# Page07_CPU_PHY.net
KiCad netlist of a schematic drawn in Altium Designer
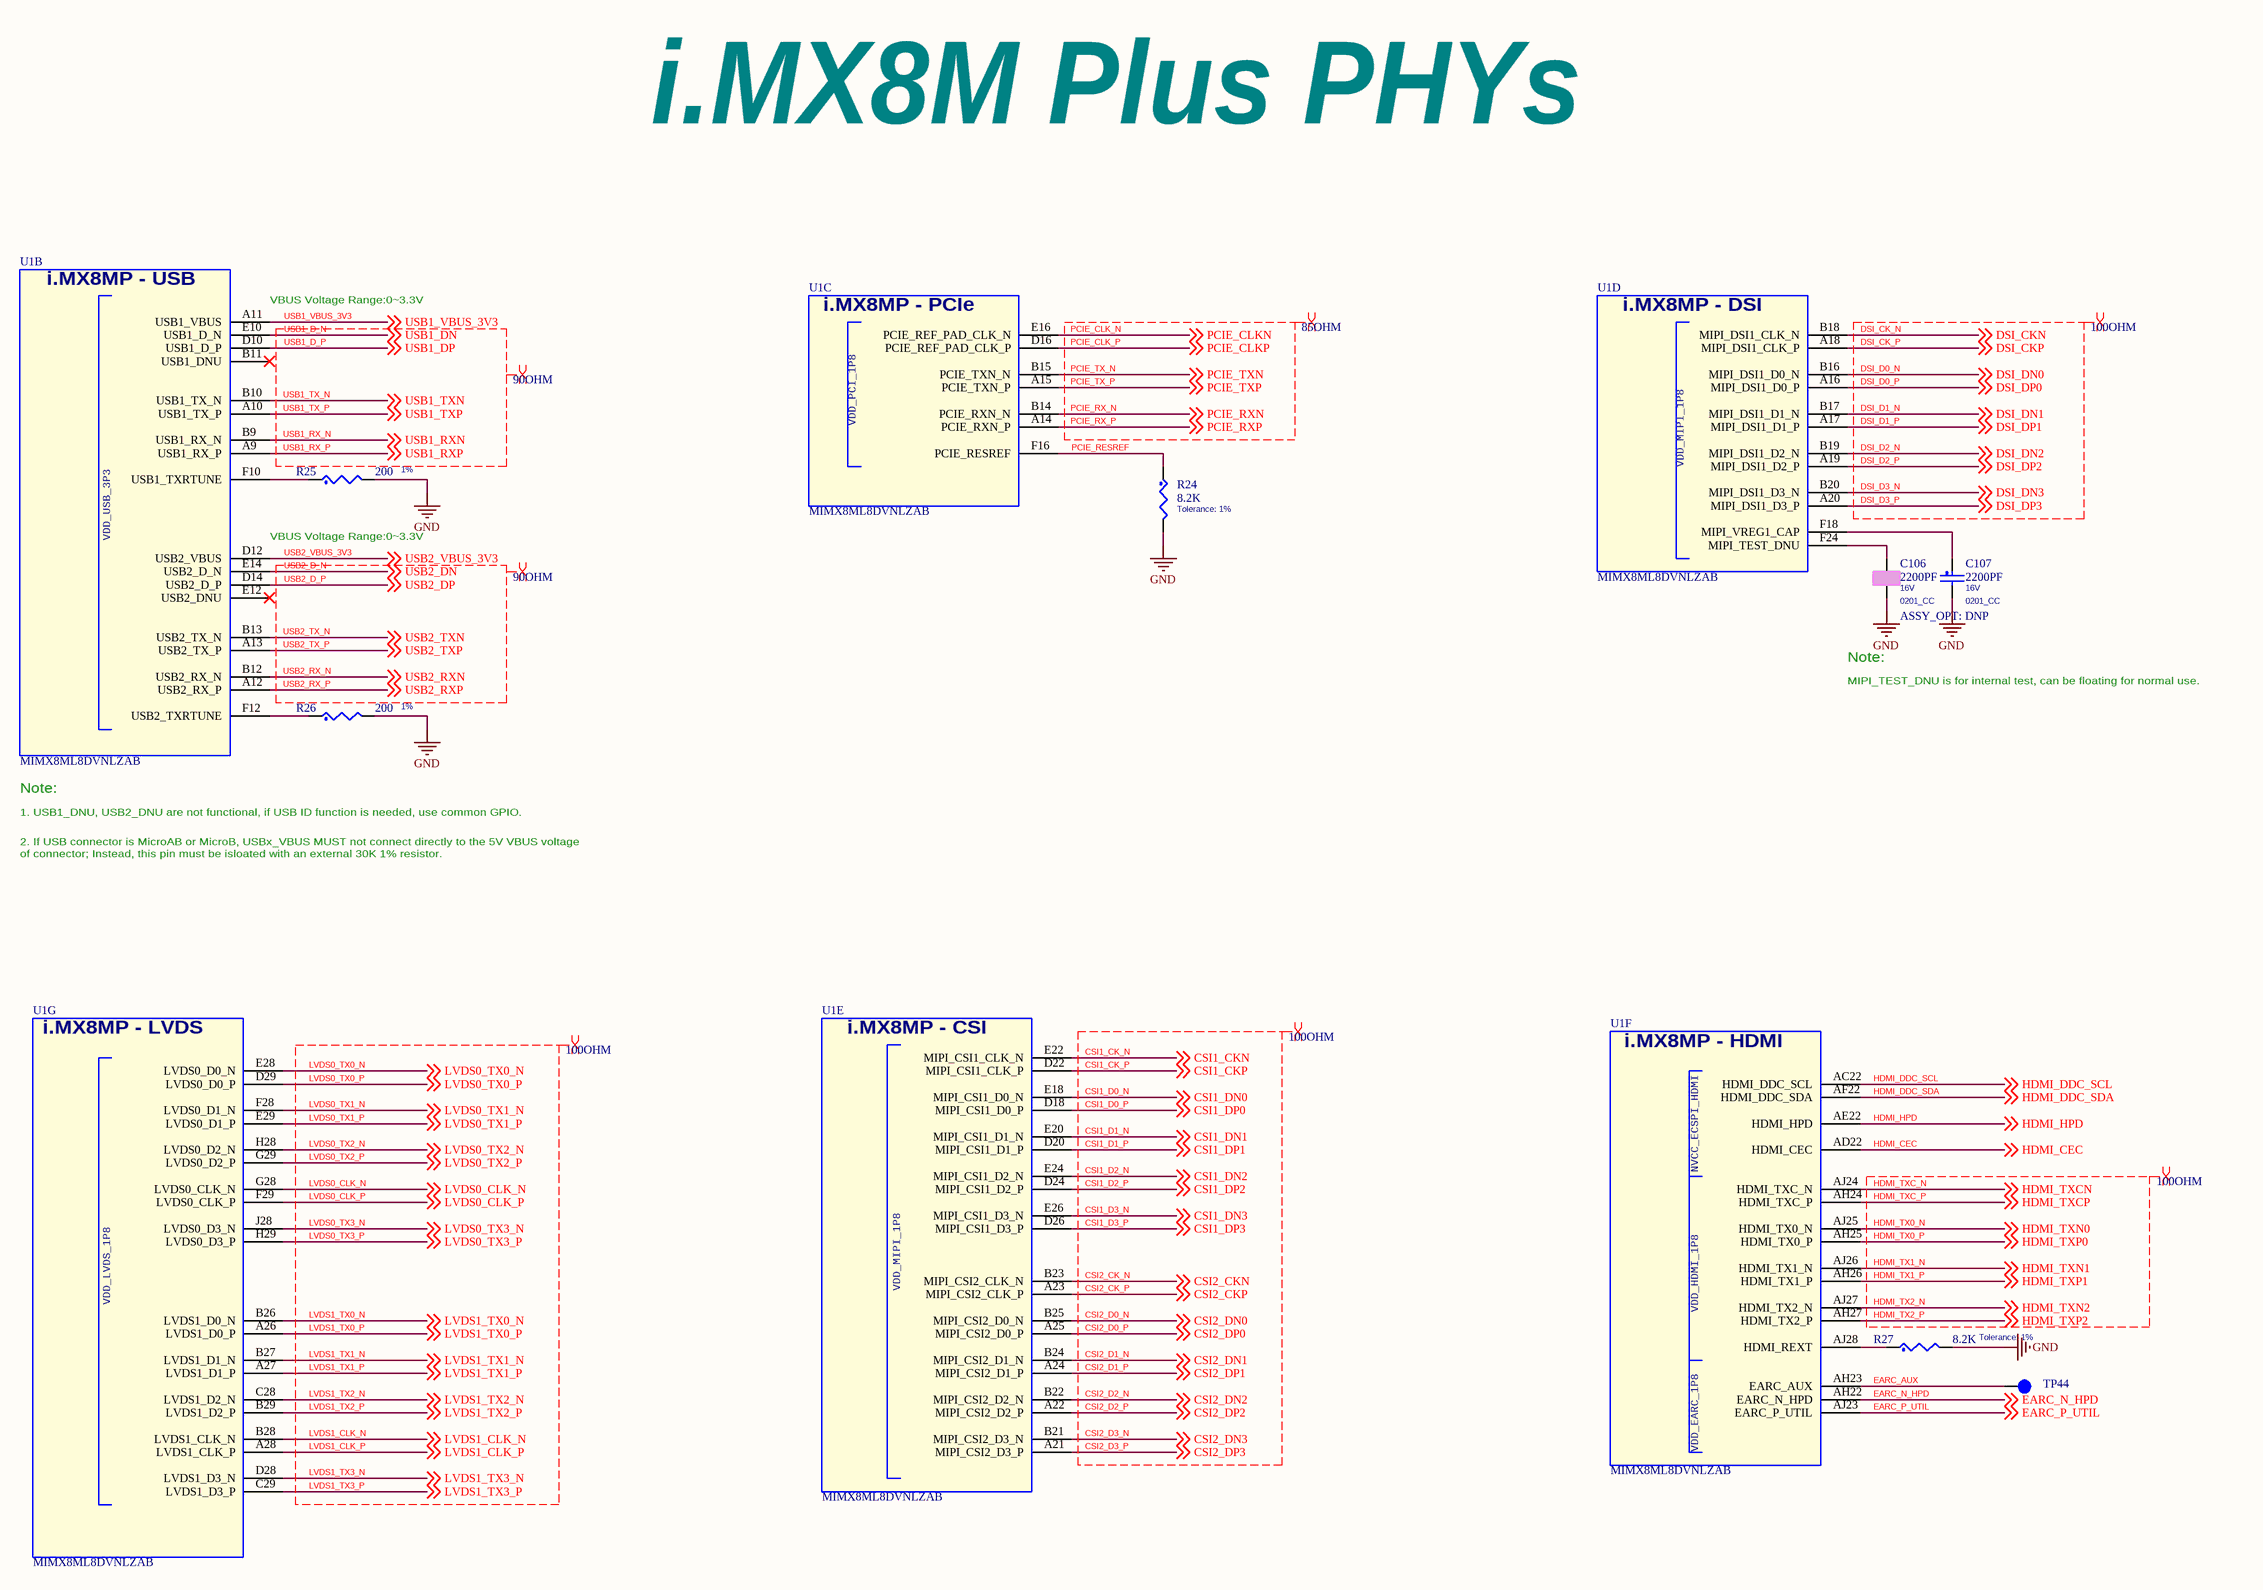
[diagram p0: Page07 CPU PHY.SchDoc]

(export (version "E")
  (design (tool "Eeschema 10.0.6"))
  (components
    (comp (ref "C106")
      (value "2200PF")
      (footprint "0201_CC")
      (description "CAP CER 2200PF 16V 10% X7R 0201")
      (fields
        (field (name "ASSY_OPT") "DNP")
        (field (name "PCB FOOTPRINT") "0201_CC")
        (field (name "VOLTAGE") "16V")
        (field (name "TOLERANCE") "20%")
      )
      (libsource (lib "*") (part "CAP_NP"))
    )
    (comp (ref "C107")
      (value "2200PF")
      (footprint "0201_CC")
      (description "CAP CER 2200PF 16V 10% X7R 0201")
      (fields
        (field (name "PCB FOOTPRINT") "0201_CC")
        (field (name "TOLERANCE") "20%")
        (field (name "VOLTAGE") "16V")
      )
      (libsource (lib "*") (part "CAP_NP"))
    )
    (comp (ref "R24")
      (value "8.2K")
      (footprint "0201_CC")
      (description "RES MF 8.2K 1/20W 1% 0201")
      (fields (field (name "TOLERANCE") "1%"))
      (libsource (lib "*") (part "RES"))
    )
    (comp (ref "R25")
      (value "200")
      (footprint "0201_CC")
      (description "RES MF 200 OHM 1/20W 1% 0201")
      (fields (field (name "TOLERANCE") "1%") (field (name "VOLTAGE") "25V"))
      (libsource (lib "*") (part "RES"))
    )
    (comp (ref "R26")
      (value "200")
      (footprint "0201_CC")
      (description "RES MF 200 OHM 1/20W 1% 0201")
      (fields (field (name "TOLERANCE") "1%") (field (name "VOLTAGE") "25V"))
      (libsource (lib "*") (part "RES"))
    )
    (comp (ref "R27")
      (value "8.2K")
      (footprint "0201_CC")
      (description "RES MF 8.2K 1/20W 1% 0201")
      (fields (field (name "TOLERANCE") "1%"))
      (libsource (lib "*") (part "RES"))
    )
    (comp (ref "TP44")
      (value "tpad_020")
      (footprint "tpad_020")
      (description "TEST POINT PAD 0.5MM DIA SMT, NO PART TO ORDER")
      (libsource (lib "*") (part "TESTLOOP"))
    )
    (comp (ref "U1")
      (value "MIMX8ML8DVNLZAB")
      (footprint "BGA_M865S_0P5_15X15-BMS")
      (description "IC CPU QUAD CORTEX A53+M4 1.8GHZ BGA548")
      (libsource (lib "*") (part "MIMX8MP_BGA548"))
    )
  )
  (nets
    (net (code "1") (name "/EARC_AUX") (class "Default")
      (node (ref "TP44") (pin "1") (pinfunction "Pin1_1") (pintype "passive"))
      (node (ref "U1") (pin "AH23") (pinfunction "EARC_AUX_AH23") (pintype "passive"))
    )
    (net (code "2") (name "/PCIE_RESREF") (class "Default")
      (node (ref "R24") (pin "1") (pinfunction "1_1") (pintype "passive"))
      (node (ref "U1") (pin "F16") (pinfunction "PCIE_RESREF_F16") (pintype "passive"))
    )
    (net (code "3") (name "CSI1_CKN") (class "Default")
      (node (ref "U1") (pin "E22") (pinfunction "MIPI_CSI1_CLK_N_E22") (pintype "passive"))
    )
    (net (code "4") (name "CSI1_CKP") (class "Default")
      (node (ref "U1") (pin "D22") (pinfunction "MIPI_CSI1_CLK_P_D22") (pintype "passive"))
    )
    (net (code "5") (name "CSI1_DN0") (class "Default")
      (node (ref "U1") (pin "E18") (pinfunction "MIPI_CSI1_D0_N_E18") (pintype "passive"))
    )
    (net (code "6") (name "CSI1_DN1") (class "Default")
      (node (ref "U1") (pin "E20") (pinfunction "MIPI_CSI1_D1_N_E20") (pintype "passive"))
    )
    (net (code "7") (name "CSI1_DN2") (class "Default")
      (node (ref "U1") (pin "E24") (pinfunction "MIPI_CSI1_D2_N_E24") (pintype "passive"))
    )
    (net (code "8") (name "CSI1_DN3") (class "Default")
      (node (ref "U1") (pin "E26") (pinfunction "MIPI_CSI1_D3_N_E26") (pintype "passive"))
    )
    (net (code "9") (name "CSI1_DP0") (class "Default")
      (node (ref "U1") (pin "D18") (pinfunction "MIPI_CSI1_D0_P_D18") (pintype "passive"))
    )
    (net (code "10") (name "CSI1_DP1") (class "Default")
      (node (ref "U1") (pin "D20") (pinfunction "MIPI_CSI1_D1_P_D20") (pintype "passive"))
    )
    (net (code "11") (name "CSI1_DP2") (class "Default")
      (node (ref "U1") (pin "D24") (pinfunction "MIPI_CSI1_D2_P_D24") (pintype "passive"))
    )
    (net (code "12") (name "CSI1_DP3") (class "Default")
      (node (ref "U1") (pin "D26") (pinfunction "MIPI_CSI1_D3_P_D26") (pintype "passive"))
    )
    (net (code "13") (name "CSI2_CKN") (class "Default")
      (node (ref "U1") (pin "B23") (pinfunction "MIPI_CSI2_CLK_N_B23") (pintype "passive"))
    )
    (net (code "14") (name "CSI2_CKP") (class "Default")
      (node (ref "U1") (pin "A23") (pinfunction "MIPI_CSI2_CLK_P_A23") (pintype "passive"))
    )
    (net (code "15") (name "CSI2_DN0") (class "Default")
      (node (ref "U1") (pin "B25") (pinfunction "MIPI_CSI2_D0_N_B25") (pintype "passive"))
    )
    (net (code "16") (name "CSI2_DN1") (class "Default")
      (node (ref "U1") (pin "B24") (pinfunction "MIPI_CSI2_D1_N_B24") (pintype "passive"))
    )
    (net (code "17") (name "CSI2_DN2") (class "Default")
      (node (ref "U1") (pin "B22") (pinfunction "MIPI_CSI2_D2_N_B22") (pintype "passive"))
    )
    (net (code "18") (name "CSI2_DN3") (class "Default")
      (node (ref "U1") (pin "B21") (pinfunction "MIPI_CSI2_D3_N_B21") (pintype "passive"))
    )
    (net (code "19") (name "CSI2_DP0") (class "Default")
      (node (ref "U1") (pin "A25") (pinfunction "MIPI_CSI2_D0_P_A25") (pintype "passive"))
    )
    (net (code "20") (name "CSI2_DP1") (class "Default")
      (node (ref "U1") (pin "A24") (pinfunction "MIPI_CSI2_D1_P_A24") (pintype "passive"))
    )
    (net (code "21") (name "CSI2_DP2") (class "Default")
      (node (ref "U1") (pin "A22") (pinfunction "MIPI_CSI2_D2_P_A22") (pintype "passive"))
    )
    (net (code "22") (name "CSI2_DP3") (class "Default")
      (node (ref "U1") (pin "A21") (pinfunction "MIPI_CSI2_D3_P_A21") (pintype "passive"))
    )
    (net (code "23") (name "DSI_CKN") (class "Default")
      (node (ref "U1") (pin "B18") (pinfunction "MIPI_DSI1_CLK_N_B18") (pintype "passive"))
    )
    (net (code "24") (name "DSI_CKP") (class "Default")
      (node (ref "U1") (pin "A18") (pinfunction "MIPI_DSI1_CLK_P_A18") (pintype "passive"))
    )
    (net (code "25") (name "DSI_DN0") (class "Default")
      (node (ref "U1") (pin "B16") (pinfunction "MIPI_DSI1_D0_N_B16") (pintype "passive"))
    )
    (net (code "26") (name "DSI_DN1") (class "Default")
      (node (ref "U1") (pin "B17") (pinfunction "MIPI_DSI1_D1_N_B17") (pintype "passive"))
    )
    (net (code "27") (name "DSI_DN2") (class "Default")
      (node (ref "U1") (pin "B19") (pinfunction "MIPI_DSI1_D2_N_B19") (pintype "passive"))
    )
    (net (code "28") (name "DSI_DN3") (class "Default")
      (node (ref "U1") (pin "B20") (pinfunction "MIPI_DSI1_D3_N_B20") (pintype "passive"))
    )
    (net (code "29") (name "DSI_DP0") (class "Default")
      (node (ref "U1") (pin "A16") (pinfunction "MIPI_DSI1_D0_P_A16") (pintype "passive"))
    )
    (net (code "30") (name "DSI_DP1") (class "Default")
      (node (ref "U1") (pin "A17") (pinfunction "MIPI_DSI1_D1_P_A17") (pintype "passive"))
    )
    (net (code "31") (name "DSI_DP2") (class "Default")
      (node (ref "U1") (pin "A19") (pinfunction "MIPI_DSI1_D2_P_A19") (pintype "passive"))
    )
    (net (code "32") (name "DSI_DP3") (class "Default")
      (node (ref "U1") (pin "A20") (pinfunction "MIPI_DSI1_D3_P_A20") (pintype "passive"))
    )
    (net (code "33") (name "EARC_N_HPD") (class "Default")
      (node (ref "U1") (pin "AH22") (pinfunction "EARC_N_HPD_AH22") (pintype "passive"))
    )
    (net (code "34") (name "EARC_P_UTIL") (class "Default")
      (node (ref "U1") (pin "AJ23") (pinfunction "EARC_P_UTIL_AJ23") (pintype "passive"))
    )
    (net (code "35") (name "GND") (class "Default")
      (node (ref "C106") (pin "2") (pinfunction "2_2") (pintype "passive"))
      (node (ref "C107") (pin "2") (pinfunction "2_2") (pintype "passive"))
      (node (ref "R24") (pin "2") (pinfunction "2_2") (pintype "passive"))
      (node (ref "R25") (pin "2") (pinfunction "2_2") (pintype "passive"))
      (node (ref "R26") (pin "2") (pinfunction "2_2") (pintype "passive"))
      (node (ref "R27") (pin "2") (pinfunction "2_2") (pintype "passive"))
    )
    (net (code "36") (name "HDMI_CEC") (class "Default")
      (node (ref "U1") (pin "AD22") (pinfunction "HDMI_CEC_AD22") (pintype "passive"))
    )
    (net (code "37") (name "HDMI_DDC_SCL") (class "Default")
      (node (ref "U1") (pin "AC22") (pinfunction "HDMI_DDC_SCL_AC22") (pintype "passive"))
    )
    (net (code "38") (name "HDMI_DDC_SDA") (class "Default")
      (node (ref "U1") (pin "AF22") (pinfunction "HDMI_DDC_SDA_AF22") (pintype "passive"))
    )
    (net (code "39") (name "HDMI_HPD") (class "Default")
      (node (ref "U1") (pin "AE22") (pinfunction "HDMI_HPD_AE22") (pintype "passive"))
    )
    (net (code "40") (name "HDMI_TXCN") (class "Default")
      (node (ref "U1") (pin "AJ24") (pinfunction "HDMI_TXC_N_AJ24") (pintype "passive"))
    )
    (net (code "41") (name "HDMI_TXCP") (class "Default")
      (node (ref "U1") (pin "AH24") (pinfunction "HDMI_TXC_P_AH24") (pintype "passive"))
    )
    (net (code "42") (name "HDMI_TXN0") (class "Default")
      (node (ref "U1") (pin "AJ25") (pinfunction "HDMI_TX0_N_AJ25") (pintype "passive"))
    )
    (net (code "43") (name "HDMI_TXN1") (class "Default")
      (node (ref "U1") (pin "AJ26") (pinfunction "HDMI_TX1_N_AJ26") (pintype "passive"))
    )
    (net (code "44") (name "HDMI_TXN2") (class "Default")
      (node (ref "U1") (pin "AJ27") (pinfunction "HDMI_TX2_N_AJ27") (pintype "passive"))
    )
    (net (code "45") (name "HDMI_TXP0") (class "Default")
      (node (ref "U1") (pin "AH25") (pinfunction "HDMI_TX0_P_AH25") (pintype "passive"))
    )
    (net (code "46") (name "HDMI_TXP1") (class "Default")
      (node (ref "U1") (pin "AH26") (pinfunction "HDMI_TX1_P_AH26") (pintype "passive"))
    )
    (net (code "47") (name "HDMI_TXP2") (class "Default")
      (node (ref "U1") (pin "AH27") (pinfunction "HDMI_TX2_P_AH27") (pintype "passive"))
    )
    (net (code "48") (name "LVDS0_CLK_N") (class "Default")
      (node (ref "U1") (pin "G28") (pinfunction "LVDS0_CLK_N_G28") (pintype "passive"))
    )
    (net (code "49") (name "LVDS0_CLK_P") (class "Default")
      (node (ref "U1") (pin "F29") (pinfunction "LVDS0_CLK_P_F29") (pintype "passive"))
    )
    (net (code "50") (name "LVDS0_TX0_N") (class "Default")
      (node (ref "U1") (pin "E28") (pinfunction "LVDS0_D0_N_E28") (pintype "passive"))
    )
    (net (code "51") (name "LVDS0_TX0_P") (class "Default")
      (node (ref "U1") (pin "D29") (pinfunction "LVDS0_D0_P_D29") (pintype "passive"))
    )
    (net (code "52") (name "LVDS0_TX1_N") (class "Default")
      (node (ref "U1") (pin "F28") (pinfunction "LVDS0_D1_N_F28") (pintype "passive"))
    )
    (net (code "53") (name "LVDS0_TX1_P") (class "Default")
      (node (ref "U1") (pin "E29") (pinfunction "LVDS0_D1_P_E29") (pintype "passive"))
    )
    (net (code "54") (name "LVDS0_TX2_N") (class "Default")
      (node (ref "U1") (pin "H28") (pinfunction "LVDS0_D2_N_H28") (pintype "passive"))
    )
    (net (code "55") (name "LVDS0_TX2_P") (class "Default")
      (node (ref "U1") (pin "G29") (pinfunction "LVDS0_D2_P_G29") (pintype "passive"))
    )
    (net (code "56") (name "LVDS0_TX3_N") (class "Default")
      (node (ref "U1") (pin "J28") (pinfunction "LVDS0_D3_N_J28") (pintype "passive"))
    )
    (net (code "57") (name "LVDS0_TX3_P") (class "Default")
      (node (ref "U1") (pin "H29") (pinfunction "LVDS0_D3_P_H29") (pintype "passive"))
    )
    (net (code "58") (name "LVDS1_CLK_N") (class "Default")
      (node (ref "U1") (pin "B28") (pinfunction "LVDS1_CLK_N_B28") (pintype "passive"))
    )
    (net (code "59") (name "LVDS1_CLK_P") (class "Default")
      (node (ref "U1") (pin "A28") (pinfunction "LVDS1_CLK_P_A28") (pintype "passive"))
    )
    (net (code "60") (name "LVDS1_TX0_N") (class "Default")
      (node (ref "U1") (pin "B26") (pinfunction "LVDS1_D0_N_B26") (pintype "passive"))
    )
    (net (code "61") (name "LVDS1_TX0_P") (class "Default")
      (node (ref "U1") (pin "A26") (pinfunction "LVDS1_D0_P_A26") (pintype "passive"))
    )
    (net (code "62") (name "LVDS1_TX1_N") (class "Default")
      (node (ref "U1") (pin "B27") (pinfunction "LVDS1_D1_N_B27") (pintype "passive"))
    )
    (net (code "63") (name "LVDS1_TX1_P") (class "Default")
      (node (ref "U1") (pin "A27") (pinfunction "LVDS1_D1_P_A27") (pintype "passive"))
    )
    (net (code "64") (name "LVDS1_TX2_N") (class "Default")
      (node (ref "U1") (pin "C28") (pinfunction "LVDS1_D2_N_C28") (pintype "passive"))
    )
    (net (code "65") (name "LVDS1_TX2_P") (class "Default")
      (node (ref "U1") (pin "B29") (pinfunction "LVDS1_D2_P_B29") (pintype "passive"))
    )
    (net (code "66") (name "LVDS1_TX3_N") (class "Default")
      (node (ref "U1") (pin "D28") (pinfunction "LVDS1_D3_N_D28") (pintype "passive"))
    )
    (net (code "67") (name "LVDS1_TX3_P") (class "Default")
      (node (ref "U1") (pin "C29") (pinfunction "LVDS1_D3_P_C29") (pintype "passive"))
    )
    (net (code "68") (name "Net-(U1B-USB1_TXRTUNE)") (class "Default")
      (node (ref "R25") (pin "1") (pinfunction "1_1") (pintype "passive"))
      (node (ref "U1") (pin "F10") (pinfunction "USB1_TXRTUNE_F10") (pintype "passive"))
    )
    (net (code "69") (name "Net-(U1B-USB2_TXRTUNE)") (class "Default")
      (node (ref "R26") (pin "1") (pinfunction "1_1") (pintype "passive"))
      (node (ref "U1") (pin "F12") (pinfunction "USB2_TXRTUNE_F12") (pintype "passive"))
    )
    (net (code "70") (name "Net-(U1D-MIPI_TEST_DNU)") (class "Default")
      (node (ref "C106") (pin "1") (pinfunction "1_1") (pintype "passive"))
      (node (ref "U1") (pin "F24") (pinfunction "MIPI_TEST_DNU_F24") (pintype "passive"))
    )
    (net (code "71") (name "Net-(U1D-MIPI_VREG1_CAP)") (class "Default")
      (node (ref "C107") (pin "1") (pinfunction "1_1") (pintype "passive"))
      (node (ref "U1") (pin "F18") (pinfunction "MIPI_VREG1_CAP_F18") (pintype "passive"))
    )
    (net (code "72") (name "Net-(U1F-HDMI_REXT)") (class "Default")
      (node (ref "R27") (pin "1") (pinfunction "1_1") (pintype "passive"))
      (node (ref "U1") (pin "AJ28") (pinfunction "HDMI_REXT_AJ28") (pintype "passive"))
    )
    (net (code "73") (name "PCIE_CLKN") (class "Default")
      (node (ref "U1") (pin "E16") (pinfunction "PCIE_REF_PAD_CLK_N_E16") (pintype "passive"))
    )
    (net (code "74") (name "PCIE_CLKP") (class "Default")
      (node (ref "U1") (pin "D16") (pinfunction "PCIE_REF_PAD_CLK_P_D16") (pintype "passive"))
    )
    (net (code "75") (name "PCIE_RXN") (class "Default")
      (node (ref "U1") (pin "B14") (pinfunction "PCIE_RXN_N_B14") (pintype "passive"))
    )
    (net (code "76") (name "PCIE_RXP") (class "Default")
      (node (ref "U1") (pin "A14") (pinfunction "PCIE_RXN_P_A14") (pintype "passive"))
    )
    (net (code "77") (name "PCIE_TXN") (class "Default")
      (node (ref "U1") (pin "B15") (pinfunction "PCIE_TXN_N_B15") (pintype "passive"))
    )
    (net (code "78") (name "PCIE_TXP") (class "Default")
      (node (ref "U1") (pin "A15") (pinfunction "PCIE_TXN_P_A15") (pintype "passive"))
    )
    (net (code "79") (name "USB1_DN") (class "Default")
      (node (ref "U1") (pin "E10") (pinfunction "USB1_D_N_E10") (pintype "passive"))
    )
    (net (code "80") (name "USB1_DP") (class "Default")
      (node (ref "U1") (pin "D10") (pinfunction "USB1_D_P_D10") (pintype "passive"))
    )
    (net (code "81") (name "USB1_RXN") (class "Default")
      (node (ref "U1") (pin "B9") (pinfunction "USB1_RX_N_B9") (pintype "passive"))
    )
    (net (code "82") (name "USB1_RXP") (class "Default")
      (node (ref "U1") (pin "A9") (pinfunction "USB1_RX_P_A9") (pintype "passive"))
    )
    (net (code "83") (name "USB1_TXN") (class "Default")
      (node (ref "U1") (pin "B10") (pinfunction "USB1_TX_N_B10") (pintype "passive"))
    )
    (net (code "84") (name "USB1_TXP") (class "Default")
      (node (ref "U1") (pin "A10") (pinfunction "USB1_TX_P_A10") (pintype "passive"))
    )
    (net (code "85") (name "USB1_VBUS_3V3") (class "Default")
      (node (ref "U1") (pin "A11") (pinfunction "USB1_VBUS_A11") (pintype "passive"))
    )
    (net (code "86") (name "USB2_DN") (class "Default")
      (node (ref "U1") (pin "E14") (pinfunction "USB2_D_N_E14") (pintype "passive"))
    )
    (net (code "87") (name "USB2_DP") (class "Default")
      (node (ref "U1") (pin "D14") (pinfunction "USB2_D_P_D14") (pintype "passive"))
    )
    (net (code "88") (name "USB2_RXN") (class "Default")
      (node (ref "U1") (pin "B12") (pinfunction "USB2_RX_N_B12") (pintype "passive"))
    )
    (net (code "89") (name "USB2_RXP") (class "Default")
      (node (ref "U1") (pin "A12") (pinfunction "USB2_RX_P_A12") (pintype "passive"))
    )
    (net (code "90") (name "USB2_TXN") (class "Default")
      (node (ref "U1") (pin "B13") (pinfunction "USB2_TX_N_B13") (pintype "passive"))
    )
    (net (code "91") (name "USB2_TXP") (class "Default")
      (node (ref "U1") (pin "A13") (pinfunction "USB2_TX_P_A13") (pintype "passive"))
    )
    (net (code "92") (name "USB2_VBUS_3V3") (class "Default")
      (node (ref "U1") (pin "D12") (pinfunction "USB2_VBUS_D12") (pintype "passive"))
    )
    (net (code "93") (name "unconnected-(U1B-USB1_DNU-PadB11)") (class "Default")
      (node (ref "U1") (pin "B11") (pinfunction "USB1_DNU_B11") (pintype "passive+no_connect"))
    )
    (net (code "94") (name "unconnected-(U1B-USB2_DNU-PadE12)") (class "Default")
      (node (ref "U1") (pin "E12") (pinfunction "USB2_DNU_E12") (pintype "passive+no_connect"))
    )
  )
)
